# RFID_Arduino_REV04.net
KiCad netlist of a schematic drawn in EasyEDA Pro
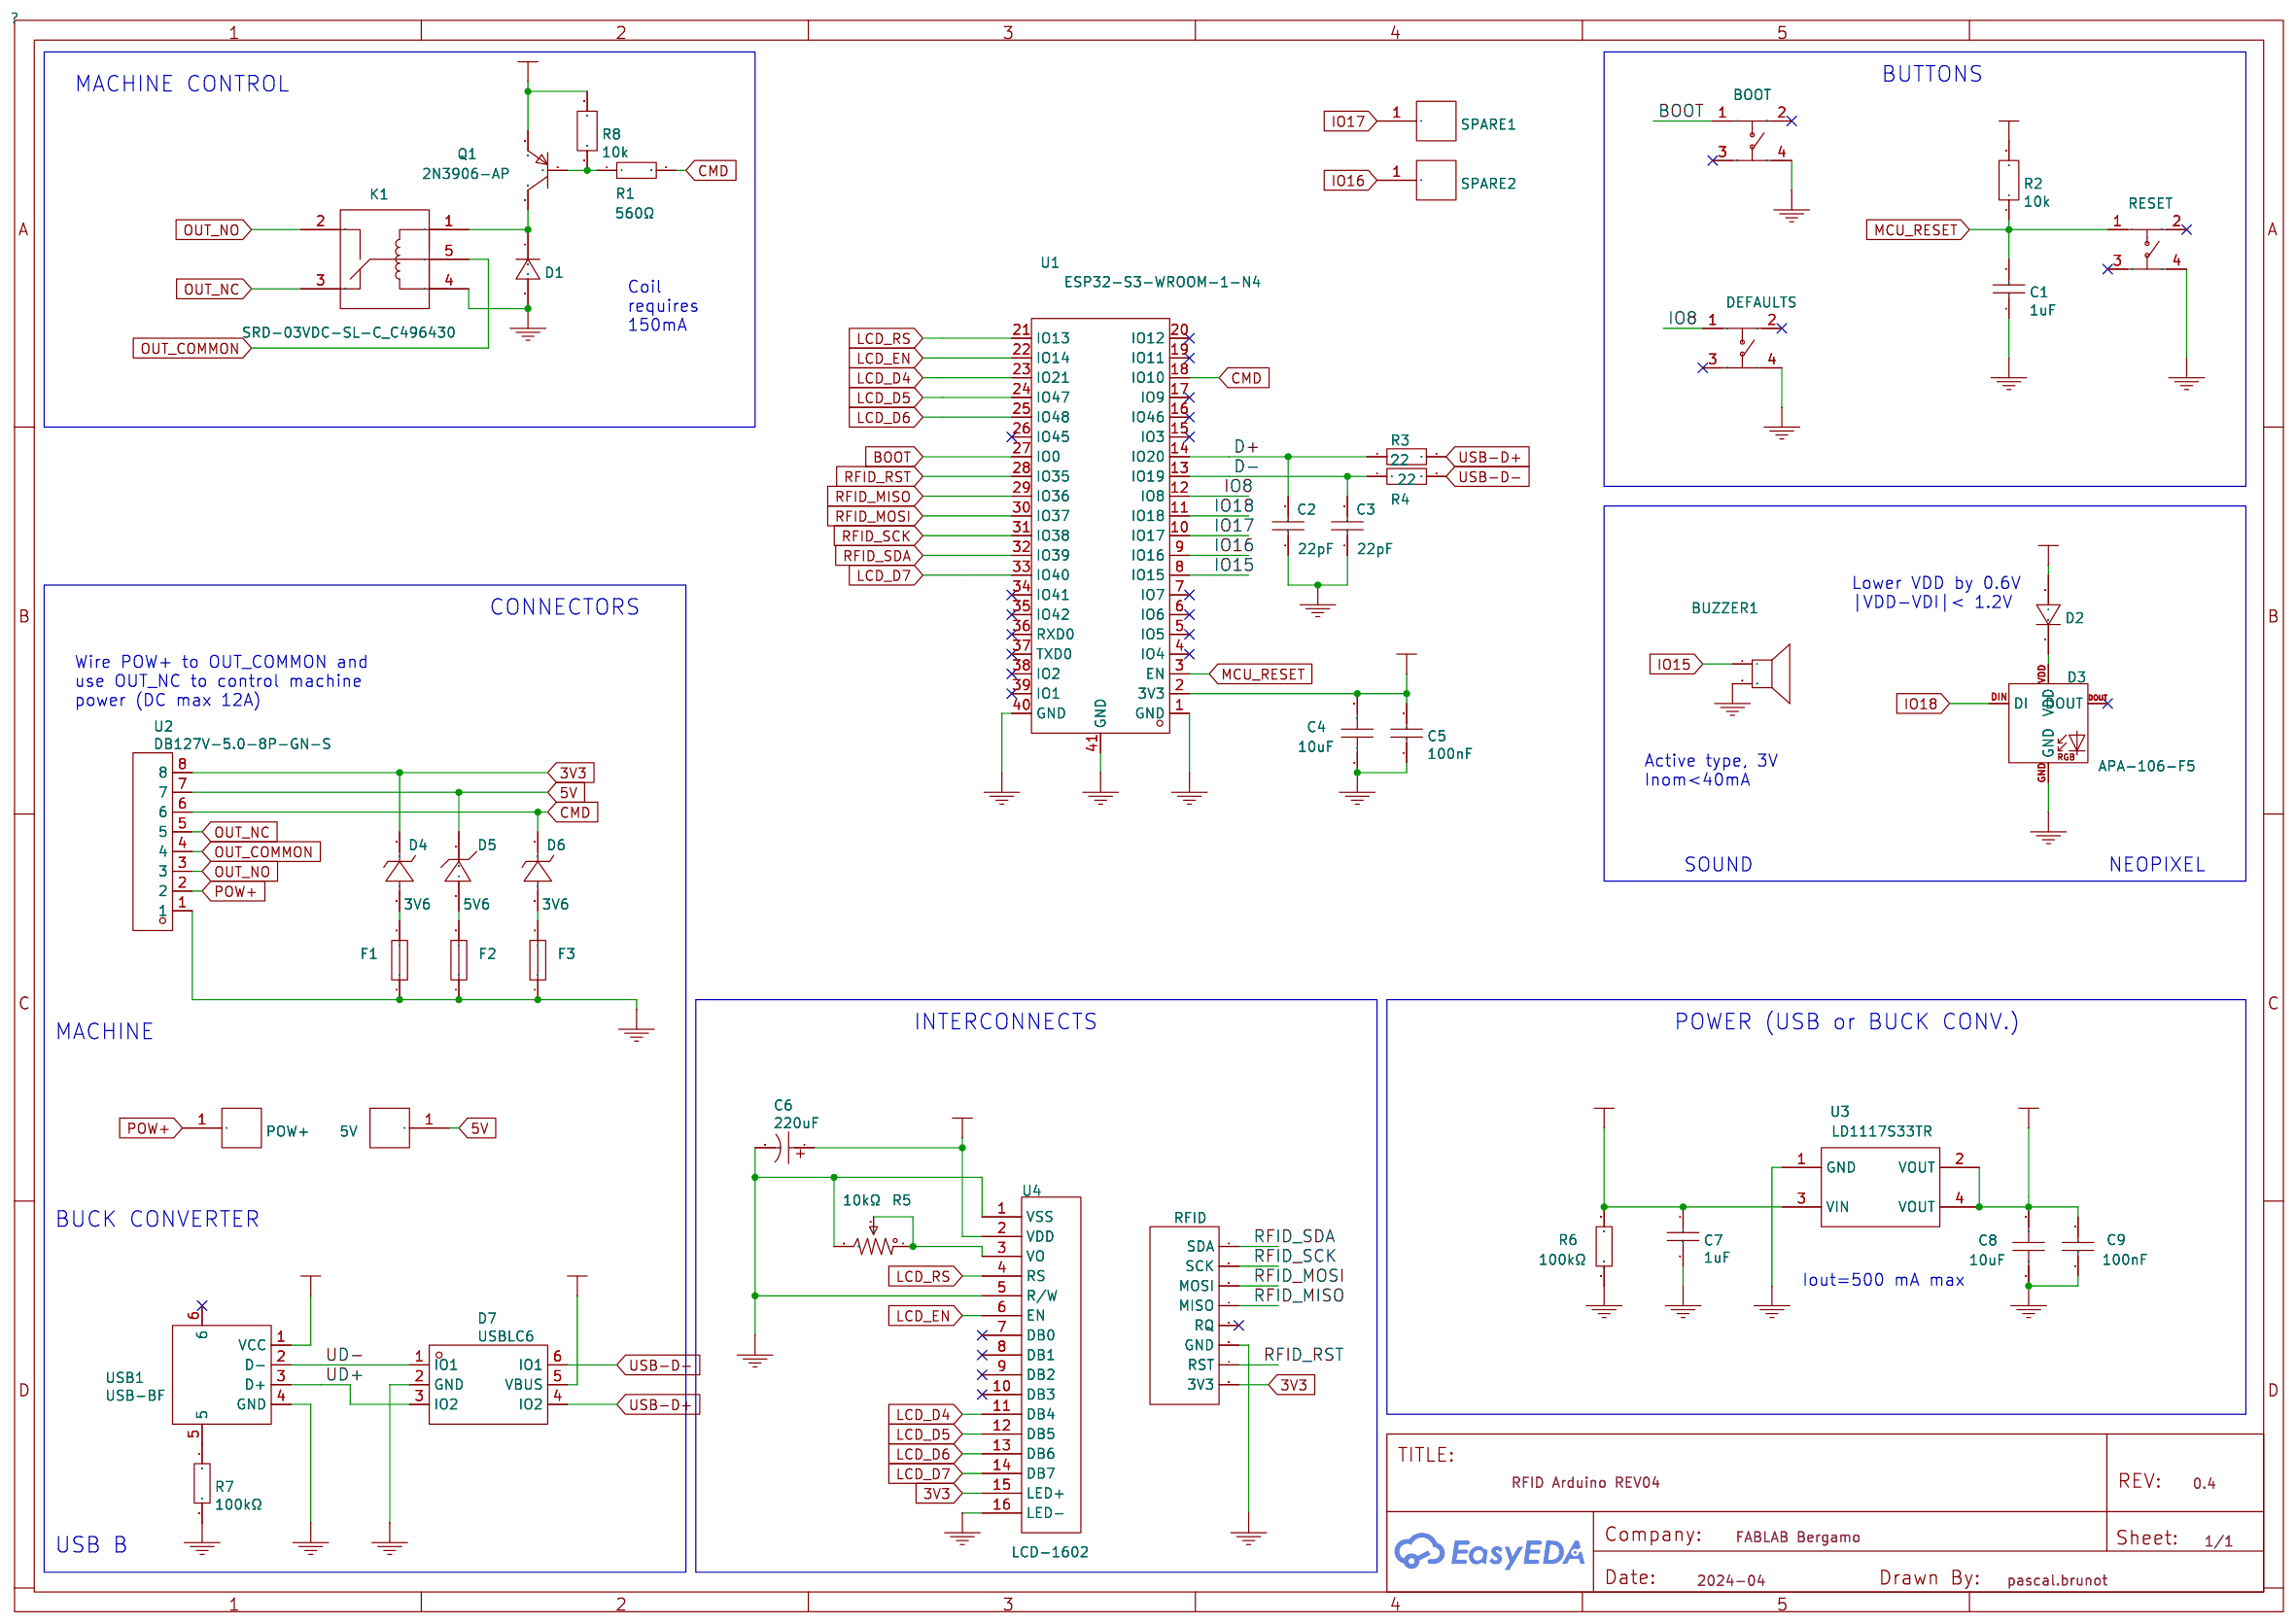
[diagram p0: schematic sheet]

(export (version "E")
  (design (tool "Eeschema 10.0.6"))
  (components
    (comp (ref "5V")
      (value "0577-0-43-80-21-27-10-0")
      (footprint "easyedapro:footprint_186c")
      (libsource (lib "easyedapro") (part "0577-0-43-80-21-27-10-0"))
    )
    (comp (ref "BOOT")
      (value "TS02-66-160-BK-260-LCR-D")
      (footprint "easyedapro:footprint_d5ca")
      (fields (field (name "Manufacturer") "CUI"))
      (libsource (lib "easyedapro") (part "TS02-66-160-BK-260-LCR-D"))
    )
    (comp (ref "BUZZER1")
      (value "4000Hz")
      (footprint "easyedapro:footprint_4700")
      (fields (field (name "Manufacturer Part") "SFN-12055PA6.5") (field (name "Manufacturer") "S&amp;S(海旭)"))
      (libsource (lib "easyedapro") (part "4000Hz"))
    )
    (comp (ref "C1")
      (value "1uF")
      (footprint "easyedapro:footprint_c612")
      (fields
        (field (name "Manufacturer Part") "CL21B105KBFNNNE")
        (field (name "Manufacturer") "SAMSUNG(三星)")
      )
      (libsource (lib "easyedapro") (part "1uF"))
    )
    (comp (ref "C2")
      (value "22pF")
      (footprint "easyedapro:footprint_7342")
      (fields (field (name "Manufacturer Part") "0402CG220J500NT") (field (name "Manufacturer") "FH(风华)"))
      (libsource (lib "easyedapro") (part "22pF"))
    )
    (comp (ref "C3")
      (value "22pF")
      (footprint "easyedapro:footprint_7342")
      (fields (field (name "Manufacturer Part") "0402CG220J500NT") (field (name "Manufacturer") "FH(风华)"))
      (libsource (lib "easyedapro") (part "22pF"))
    )
    (comp (ref "C4")
      (value "10uF")
      (footprint "easyedapro:footprint_c612")
      (fields
        (field (name "Manufacturer Part") "GRM21BR61H106KE43L")
        (field (name "Manufacturer") "muRata(村田)")
      )
      (libsource (lib "easyedapro") (part "10uF"))
    )
    (comp (ref "C5")
      (value "100nF")
      (footprint "easyedapro:footprint_c612")
      (fields
        (field (name "Manufacturer Part") "CL21B104KCFNNNE")
        (field (name "Manufacturer") "SAMSUNG(三星)")
      )
      (libsource (lib "easyedapro") (part "100nF"))
    )
    (comp (ref "C6")
      (value "220uF")
      (footprint "easyedapro:footprint_9de2")
      (fields (field (name "Manufacturer Part") "220uF 10V 5*7"))
      (libsource (lib "easyedapro") (part "220uF"))
    )
    (comp (ref "C7")
      (value "1uF")
      (footprint "easyedapro:footprint_c612")
      (fields
        (field (name "Manufacturer Part") "CL21B105KBFNNNE")
        (field (name "Manufacturer") "SAMSUNG(三星)")
      )
      (libsource (lib "easyedapro") (part "1uF"))
    )
    (comp (ref "C8")
      (value "10uF")
      (footprint "easyedapro:footprint_c612")
      (fields
        (field (name "Manufacturer Part") "GRM21BR61H106KE43L")
        (field (name "Manufacturer") "muRata(村田)")
      )
      (libsource (lib "easyedapro") (part "10uF"))
    )
    (comp (ref "C9")
      (value "100nF")
      (footprint "easyedapro:footprint_c612")
      (fields
        (field (name "Manufacturer Part") "CL21B104KCFNNNE")
        (field (name "Manufacturer") "SAMSUNG(三星)")
      )
      (libsource (lib "easyedapro") (part "100nF"))
    )
    (comp (ref "D1")
      (value "SM4007PL")
      (footprint "easyedapro:footprint_98a7")
      (fields (field (name "Manufacturer") "MDD"))
      (libsource (lib "easyedapro") (part "SM4007PL"))
    )
    (comp (ref "D2")
      (value "SM4007PL")
      (footprint "easyedapro:footprint_98a7")
      (fields (field (name "Manufacturer") "MDD"))
      (libsource (lib "easyedapro") (part "SM4007PL"))
    )
    (comp (ref "D3")
      (value "APA-106-F5")
      (footprint "easyedapro:footprint_7df5")
      (libsource (lib "easyedapro") (part "APA-106-F5"))
    )
    (comp (ref "D4")
      (value "3V6")
      (footprint "easyedapro:footprint_9df2")
      (fields (field (name "Manufacturer Part") "1SMA5914A") (field (name "Manufacturer") "LGE(鲁光)"))
      (libsource (lib "easyedapro") (part "3V6"))
    )
    (comp (ref "D5")
      (value "5V6")
      (footprint "easyedapro:footprint_7d78")
      (fields (field (name "Manufacturer Part") "ZMM5V6-M") (field (name "Manufacturer") "ST(先科)"))
      (libsource (lib "easyedapro") (part "5V6"))
    )
    (comp (ref "D6")
      (value "3V6")
      (footprint "easyedapro:footprint_9df2")
      (fields (field (name "Manufacturer Part") "1SMA5914A") (field (name "Manufacturer") "LGE(鲁光)"))
      (libsource (lib "easyedapro") (part "3V6"))
    )
    (comp (ref "D7")
      (value "USBLC6")
      (footprint "easyedapro:footprint_c63f")
      (fields
        (field (name "Manufacturer Part") "USBLC6-2SC6")
        (field (name "Manufacturer") "TECH PUBLIC(台舟)")
      )
      (libsource (lib "easyedapro") (part "USBLC6"))
    )
    (comp (ref "DEFAULTS")
      (value "TS02-66-160-BK-260-LCR-D")
      (footprint "easyedapro:footprint_d5ca")
      (fields (field (name "Manufacturer") "CUI"))
      (libsource (lib "easyedapro") (part "TS02-66-160-BK-260-LCR-D"))
    )
    (comp (ref "F1")
      (value "1206L016WR")
      (footprint "easyedapro:footprint_80a4")
      (fields (field (name "Manufacturer") "Littelfuse(美国力特)"))
      (libsource (lib "easyedapro") (part "1206L016WR"))
    )
    (comp (ref "F2")
      (value "1206L016WR")
      (footprint "easyedapro:footprint_80a4")
      (fields (field (name "Manufacturer") "Littelfuse(美国力特)"))
      (libsource (lib "easyedapro") (part "1206L016WR"))
    )
    (comp (ref "F3")
      (value "1206L016WR")
      (footprint "easyedapro:footprint_80a4")
      (fields (field (name "Manufacturer") "Littelfuse(美国力特)"))
      (libsource (lib "easyedapro") (part "1206L016WR"))
    )
    (comp (ref "K1")
      (value "SRD-03VDC-SL-C_C496430")
      (footprint "easyedapro:footprint_073f")
      (fields (field (name "Manufacturer Part") "SRD-03VDC-SL-C") (field (name "Manufacturer") "松乐"))
      (libsource (lib "easyedapro") (part "SRD-03VDC-SL-C_C496430"))
    )
    (comp (ref "P1")
      (value "RFID")
      (footprint "easyedapro:footprint_407f")
      (fields
        (field (name "Manufacturer Part") "Female headerHDR1X8-2.54")
        (field (name "Manufacturer") "BOOMELE")
      )
      (libsource (lib "easyedapro") (part "RFID"))
    )
    (comp (ref "POW+")
      (value "0577-0-43-80-21-27-10-0")
      (footprint "easyedapro:footprint_186c")
      (libsource (lib "easyedapro") (part "0577-0-43-80-21-27-10-0"))
    )
    (comp (ref "Q1")
      (value "2N3906-AP")
      (footprint "easyedapro:footprint_6217")
      (fields (field (name "Manufacturer") "MCC(美微科)"))
      (libsource (lib "easyedapro") (part "2N3906-AP"))
    )
    (comp (ref "R1")
      (value "560Ω")
      (footprint "easyedapro:footprint_ec5b")
      (fields
        (field (name "Manufacturer Part") "0805W8F5600T5E")
        (field (name "Manufacturer") "UNI-ROYAL(厚声)")
      )
      (libsource (lib "easyedapro") (part "560Ω"))
    )
    (comp (ref "R2")
      (value "10k")
      (footprint "easyedapro:footprint_7623")
      (fields
        (field (name "Manufacturer Part") "0805W8F1002T5E")
        (field (name "Manufacturer") "UNI-ROYAL(厚声)")
      )
      (libsource (lib "easyedapro") (part "10k"))
    )
    (comp (ref "R3")
      (value "22")
      (footprint "easyedapro:footprint_7623")
      (fields
        (field (name "Manufacturer Part") "0603WAF220JT5E")
        (field (name "Manufacturer") "UNI-ROYAL(厚声)")
      )
      (libsource (lib "easyedapro") (part "22"))
    )
    (comp (ref "R4")
      (value "22")
      (footprint "easyedapro:footprint_7623")
      (fields
        (field (name "Manufacturer Part") "0603WAF220JT5E")
        (field (name "Manufacturer") "UNI-ROYAL(厚声)")
      )
      (libsource (lib "easyedapro") (part "22"))
    )
    (comp (ref "R5")
      (value "10kΩ")
      (footprint "easyedapro:footprint_ac57")
      (fields (field (name "Manufacturer Part") "3296W-1-103") (field (name "Manufacturer") "BOCHEN(博晨)"))
      (libsource (lib "easyedapro") (part "10kΩ"))
    )
    (comp (ref "R6")
      (value "100kΩ")
      (footprint "easyedapro:footprint_ec5b")
      (fields
        (field (name "Manufacturer Part") "0805W8F1003T5E")
        (field (name "Manufacturer") "UNI-ROYAL(厚声)")
      )
      (libsource (lib "easyedapro") (part "100kΩ"))
    )
    (comp (ref "R7")
      (value "100kΩ")
      (footprint "easyedapro:footprint_ec5b")
      (fields
        (field (name "Manufacturer Part") "0805W8F1003T5E")
        (field (name "Manufacturer") "UNI-ROYAL(厚声)")
      )
      (libsource (lib "easyedapro") (part "100kΩ"))
    )
    (comp (ref "R8")
      (value "10k")
      (footprint "easyedapro:footprint_7623")
      (fields
        (field (name "Manufacturer Part") "0805W8F1002T5E")
        (field (name "Manufacturer") "UNI-ROYAL(厚声)")
      )
      (libsource (lib "easyedapro") (part "10k"))
    )
    (comp (ref "RESET")
      (value "TS02-66-160-BK-260-LCR-D")
      (footprint "easyedapro:footprint_d5ca")
      (fields (field (name "Manufacturer") "CUI"))
      (libsource (lib "easyedapro") (part "TS02-66-160-BK-260-LCR-D"))
    )
    (comp (ref "SPARE1")
      (value "0577-0-43-80-21-27-10-0")
      (footprint "easyedapro:footprint_186c")
      (libsource (lib "easyedapro") (part "0577-0-43-80-21-27-10-0"))
    )
    (comp (ref "SPARE2")
      (value "0577-0-43-80-21-27-10-0")
      (footprint "easyedapro:footprint_186c")
      (libsource (lib "easyedapro") (part "0577-0-43-80-21-27-10-0"))
    )
    (comp (ref "U1")
      (value "ESP32-S3-WROOM-1-N4")
      (footprint "easyedapro:footprint_15fb")
      (fields (field (name "Manufacturer") "ESPRESSIF(乐鑫)"))
      (libsource (lib "easyedapro") (part "ESP32-S3-WROOM-1-N4"))
    )
    (comp (ref "U2")
      (value "DB127V-5.0-8P-GN-S")
      (footprint "easyedapro:footprint_3f91")
      (fields (field (name "Manufacturer") "DORABO(地博电气)"))
      (libsource (lib "easyedapro") (part "DB127V-5.0-8P-GN-S"))
    )
    (comp (ref "U3")
      (value "LD1117S33TR")
      (footprint "easyedapro:footprint_bf77")
      (fields (field (name "Manufacturer") "ST(意法半导体)"))
      (libsource (lib "easyedapro") (part "LD1117S33TR"))
    )
    (comp (ref "U4")
      (value "LCD-1602")
      (footprint "easyedapro:footprint_ddb7")
      (fields (field (name "Manufacturer Part") "?"))
      (libsource (lib "easyedapro") (part "LCD-1602"))
    )
    (comp (ref "USB1")
      (value "USB-BF")
      (footprint "easyedapro:footprint_8114")
      (fields (field (name "Manufacturer Part") "670688000") (field (name "Manufacturer") "MOLEX"))
      (libsource (lib "easyedapro") (part "USB-BF"))
    )
  )
  (nets
    (net (code "1") (name "/D+") (class "Default")
      (node (ref "C2") (pin "2") (pinfunction "2_2") (pintype "input"))
      (node (ref "R3") (pin "1") (pinfunction "1_1") (pintype "input"))
      (node (ref "U1") (pin "14") (pinfunction "IO20_14") (pintype "unspecified"))
    )
    (net (code "2") (name "/D-") (class "Default")
      (node (ref "C3") (pin "2") (pinfunction "2_2") (pintype "input"))
      (node (ref "R4") (pin "1") (pinfunction "1_1") (pintype "input"))
      (node (ref "U1") (pin "13") (pinfunction "IO19_13") (pintype "unspecified"))
    )
    (net (code "3") (name "/IO8") (class "Default")
      (node (ref "DEFAULTS") (pin "1") (pinfunction "1_1") (pintype "unspecified"))
      (node (ref "U1") (pin "12") (pinfunction "IO8_12") (pintype "unspecified"))
    )
    (net (code "4") (name "/UD+") (class "Default")
      (node (ref "D7") (pin "3") (pinfunction "IO2_3") (pintype "unspecified"))
      (node (ref "USB1") (pin "3") (pinfunction "D+_3") (pintype "unspecified"))
    )
    (net (code "5") (name "/UD-") (class "Default")
      (node (ref "D7") (pin "1") (pinfunction "IO1_1") (pintype "unspecified"))
      (node (ref "USB1") (pin "2") (pinfunction "D-_2") (pintype "unspecified"))
    )
    (net (code "6") (name "3V3") (class "Default")
      (node (ref "C4") (pin "2") (pinfunction "2_2") (pintype "unspecified"))
      (node (ref "C5") (pin "2") (pinfunction "2_2") (pintype "input"))
      (node (ref "C8") (pin "2") (pinfunction "2_2") (pintype "unspecified"))
      (node (ref "C9") (pin "2") (pinfunction "2_2") (pintype "input"))
      (node (ref "D4") (pin "1") (pinfunction "C_1") (pintype "unspecified"))
      (node (ref "P1") (pin "8") (pinfunction "3V3_8") (pintype "input"))
      (node (ref "Q1") (pin "1") (pinfunction "1_1") (pintype "input"))
      (node (ref "R2") (pin "2") (pinfunction "2_2") (pintype "unspecified"))
      (node (ref "R8") (pin "2") (pinfunction "2_2") (pintype "unspecified"))
      (node (ref "U1") (pin "2") (pinfunction "3V3_2") (pintype "unspecified"))
      (node (ref "U2") (pin "8") (pinfunction "8_8") (pintype "unspecified"))
      (node (ref "U3") (pin "2") (pinfunction "VOUT_2") (pintype "unspecified"))
      (node (ref "U3") (pin "4") (pinfunction "VOUT_4") (pintype "unspecified"))
      (node (ref "U4") (pin "15") (pinfunction "LED+_15") (pintype "unspecified"))
    )
    (net (code "7") (name "5V") (class "Default")
      (node (ref "5V") (pin "1") (pinfunction "1_1") (pintype "unspecified"))
      (node (ref "C6") (pin "1") (pinfunction "1_1") (pintype "input"))
      (node (ref "C7") (pin "1") (pinfunction "1_1") (pintype "input"))
      (node (ref "D2") (pin "2") (pinfunction "A_2") (pintype "unspecified"))
      (node (ref "D5") (pin "1") (pinfunction "C_1") (pintype "unspecified"))
      (node (ref "D7") (pin "5") (pinfunction "VBUS_5") (pintype "unspecified"))
      (node (ref "R6") (pin "2") (pinfunction "2_2") (pintype "unspecified"))
      (node (ref "U2") (pin "7") (pinfunction "7_7") (pintype "unspecified"))
      (node (ref "U3") (pin "3") (pinfunction "VIN_3") (pintype "unspecified"))
      (node (ref "U4") (pin "2") (pinfunction "VDD_2") (pintype "unspecified"))
      (node (ref "USB1") (pin "1") (pinfunction "VCC_1") (pintype "unspecified"))
    )
    (net (code "8") (name "BOOT") (class "Default")
      (node (ref "BOOT") (pin "1") (pinfunction "1_1") (pintype "unspecified"))
      (node (ref "U1") (pin "27") (pinfunction "IO0_27") (pintype "unspecified"))
    )
    (net (code "9") (name "CMD") (class "Default")
      (node (ref "D6") (pin "1") (pinfunction "C_1") (pintype "unspecified"))
      (node (ref "R1") (pin "2") (pinfunction "2_2") (pintype "input"))
      (node (ref "U1") (pin "18") (pinfunction "IO10_18") (pintype "unspecified"))
      (node (ref "U2") (pin "6") (pinfunction "6_6") (pintype "unspecified"))
    )
    (net (code "10") (name "GND") (class "Default")
      (node (ref "BOOT") (pin "4") (pinfunction "4_4") (pintype "unspecified"))
      (node (ref "BUZZER1") (pin "2") (pinfunction "2_2") (pintype "unspecified"))
      (node (ref "C1") (pin "1") (pinfunction "1_1") (pintype "input"))
      (node (ref "C2") (pin "1") (pinfunction "1_1") (pintype "input"))
      (node (ref "C3") (pin "1") (pinfunction "1_1") (pintype "input"))
      (node (ref "C4") (pin "1") (pinfunction "1_1") (pintype "unspecified"))
      (node (ref "C5") (pin "1") (pinfunction "1_1") (pintype "input"))
      (node (ref "C6") (pin "2") (pinfunction "2_2") (pintype "input"))
      (node (ref "C7") (pin "2") (pinfunction "2_2") (pintype "input"))
      (node (ref "C8") (pin "1") (pinfunction "1_1") (pintype "unspecified"))
      (node (ref "C9") (pin "1") (pinfunction "1_1") (pintype "input"))
      (node (ref "D1") (pin "2") (pinfunction "A_2") (pintype "unspecified"))
      (node (ref "D3") (pin "GND") (pinfunction "GND_GND") (pintype "bidirectional"))
      (node (ref "D7") (pin "2") (pinfunction "GND_2") (pintype "unspecified"))
      (node (ref "DEFAULTS") (pin "4") (pinfunction "4_4") (pintype "unspecified"))
      (node (ref "F1") (pin "1") (pinfunction "1_1") (pintype "unspecified"))
      (node (ref "F2") (pin "1") (pinfunction "1_1") (pintype "unspecified"))
      (node (ref "F3") (pin "1") (pinfunction "1_1") (pintype "unspecified"))
      (node (ref "K1") (pin "4") (pinfunction "4_4") (pintype "unspecified"))
      (node (ref "P1") (pin "6") (pinfunction "GND_6") (pintype "input"))
      (node (ref "R5") (pin "3") (pinfunction "3_3") (pintype "unspecified"))
      (node (ref "R6") (pin "1") (pinfunction "1_1") (pintype "unspecified"))
      (node (ref "R7") (pin "2") (pinfunction "2_2") (pintype "unspecified"))
      (node (ref "RESET") (pin "4") (pinfunction "4_4") (pintype "unspecified"))
      (node (ref "U1") (pin "1") (pinfunction "GND_1") (pintype "unspecified"))
      (node (ref "U1") (pin "40") (pinfunction "GND_40") (pintype "unspecified"))
      (node (ref "U1") (pin "41") (pinfunction "GND_41") (pintype "unspecified"))
      (node (ref "U2") (pin "1") (pinfunction "1_1") (pintype "unspecified"))
      (node (ref "U3") (pin "1") (pinfunction "GND_1") (pintype "unspecified"))
      (node (ref "U4") (pin "1") (pinfunction "VSS_1") (pintype "unspecified"))
      (node (ref "U4") (pin "16") (pinfunction "LED-_16") (pintype "unspecified"))
      (node (ref "U4") (pin "5") (pinfunction "R/W_5") (pintype "unspecified"))
      (node (ref "USB1") (pin "4") (pinfunction "GND_4") (pintype "unspecified"))
    )
    (net (code "11") (name "IO15") (class "Default")
      (node (ref "BUZZER1") (pin "1") (pinfunction "1_1") (pintype "unspecified"))
      (node (ref "U1") (pin "8") (pinfunction "IO15_8") (pintype "unspecified"))
    )
    (net (code "12") (name "IO16") (class "Default")
      (node (ref "SPARE2") (pin "1") (pinfunction "1_1") (pintype "unspecified"))
      (node (ref "U1") (pin "9") (pinfunction "IO16_9") (pintype "unspecified"))
    )
    (net (code "13") (name "IO17") (class "Default")
      (node (ref "SPARE1") (pin "1") (pinfunction "1_1") (pintype "unspecified"))
      (node (ref "U1") (pin "10") (pinfunction "IO17_10") (pintype "unspecified"))
    )
    (net (code "14") (name "IO18") (class "Default")
      (node (ref "D3") (pin "DIN") (pinfunction "DI_DIN") (pintype "input"))
      (node (ref "U1") (pin "11") (pinfunction "IO18_11") (pintype "unspecified"))
    )
    (net (code "15") (name "LCD_D4") (class "Default")
      (node (ref "U1") (pin "23") (pinfunction "IO21_23") (pintype "unspecified"))
      (node (ref "U4") (pin "11") (pinfunction "DB4_11") (pintype "unspecified"))
    )
    (net (code "16") (name "LCD_D5") (class "Default")
      (node (ref "U1") (pin "24") (pinfunction "IO47_24") (pintype "unspecified"))
      (node (ref "U4") (pin "12") (pinfunction "DB5_12") (pintype "unspecified"))
    )
    (net (code "17") (name "LCD_D6") (class "Default")
      (node (ref "U1") (pin "25") (pinfunction "IO48_25") (pintype "unspecified"))
      (node (ref "U4") (pin "13") (pinfunction "DB6_13") (pintype "unspecified"))
    )
    (net (code "18") (name "LCD_D7") (class "Default")
      (node (ref "U1") (pin "33") (pinfunction "IO40_33") (pintype "unspecified"))
      (node (ref "U4") (pin "14") (pinfunction "DB7_14") (pintype "unspecified"))
    )
    (net (code "19") (name "LCD_EN") (class "Default")
      (node (ref "U1") (pin "22") (pinfunction "IO14_22") (pintype "unspecified"))
      (node (ref "U4") (pin "6") (pinfunction "EN_6") (pintype "unspecified"))
    )
    (net (code "20") (name "LCD_RS") (class "Default")
      (node (ref "U1") (pin "21") (pinfunction "IO13_21") (pintype "unspecified"))
      (node (ref "U4") (pin "4") (pinfunction "RS_4") (pintype "unspecified"))
    )
    (net (code "21") (name "MCU_RESET") (class "Default")
      (node (ref "C1") (pin "2") (pinfunction "2_2") (pintype "input"))
      (node (ref "R2") (pin "1") (pinfunction "1_1") (pintype "unspecified"))
      (node (ref "RESET") (pin "1") (pinfunction "1_1") (pintype "unspecified"))
      (node (ref "U1") (pin "3") (pinfunction "EN_3") (pintype "unspecified"))
    )
    (net (code "22") (name "Net-(D1-C)") (class "Default")
      (node (ref "D1") (pin "1") (pinfunction "C_1") (pintype "unspecified"))
      (node (ref "K1") (pin "1") (pinfunction "1_1") (pintype "unspecified"))
      (node (ref "Q1") (pin "3") (pinfunction "3_3") (pintype "input"))
    )
    (net (code "23") (name "Net-(D2-C)") (class "Default")
      (node (ref "D2") (pin "1") (pinfunction "C_1") (pintype "unspecified"))
      (node (ref "D3") (pin "VDD") (pinfunction "VDD_VDD") (pintype "bidirectional"))
    )
    (net (code "24") (name "Net-(D4-A)") (class "Default")
      (node (ref "D4") (pin "2") (pinfunction "A_2") (pintype "unspecified"))
      (node (ref "F1") (pin "2") (pinfunction "2_2") (pintype "unspecified"))
    )
    (net (code "25") (name "Net-(D5-A)") (class "Default")
      (node (ref "D5") (pin "2") (pinfunction "A_2") (pintype "unspecified"))
      (node (ref "F2") (pin "2") (pinfunction "2_2") (pintype "unspecified"))
    )
    (net (code "26") (name "Net-(D6-A)") (class "Default")
      (node (ref "D6") (pin "2") (pinfunction "A_2") (pintype "unspecified"))
      (node (ref "F3") (pin "2") (pinfunction "2_2") (pintype "unspecified"))
    )
    (net (code "27") (name "Net-(Q1-Pad2)") (class "Default")
      (node (ref "Q1") (pin "2") (pinfunction "2_2") (pintype "input"))
      (node (ref "R1") (pin "1") (pinfunction "1_1") (pintype "input"))
      (node (ref "R8") (pin "1") (pinfunction "1_1") (pintype "unspecified"))
    )
    (net (code "28") (name "Net-(R7-Pad1)") (class "Default")
      (node (ref "R7") (pin "1") (pinfunction "1_1") (pintype "unspecified"))
      (node (ref "USB1") (pin "5") (pinfunction "5_5") (pintype "unspecified"))
    )
    (net (code "29") (name "Net-(U4-VO)") (class "Default")
      (node (ref "R5") (pin "1") (pinfunction "1_1") (pintype "unspecified"))
      (node (ref "R5") (pin "2") (pinfunction "2_2") (pintype "unspecified"))
      (node (ref "U4") (pin "3") (pinfunction "VO_3") (pintype "unspecified"))
    )
    (net (code "30") (name "OUT_COMMON") (class "Default")
      (node (ref "K1") (pin "5") (pinfunction "5_5") (pintype "unspecified"))
      (node (ref "U2") (pin "4") (pinfunction "4_4") (pintype "unspecified"))
    )
    (net (code "31") (name "OUT_NC") (class "Default")
      (node (ref "K1") (pin "3") (pinfunction "3_3") (pintype "unspecified"))
      (node (ref "U2") (pin "5") (pinfunction "5_5") (pintype "unspecified"))
    )
    (net (code "32") (name "OUT_NO") (class "Default")
      (node (ref "K1") (pin "2") (pinfunction "2_2") (pintype "unspecified"))
      (node (ref "U2") (pin "3") (pinfunction "3_3") (pintype "unspecified"))
    )
    (net (code "33") (name "POW+") (class "Default")
      (node (ref "POW+") (pin "1") (pinfunction "1_1") (pintype "unspecified"))
      (node (ref "U2") (pin "2") (pinfunction "2_2") (pintype "unspecified"))
    )
    (net (code "34") (name "RFID_MISO") (class "Default")
      (node (ref "P1") (pin "4") (pinfunction "MISO_4") (pintype "input"))
      (node (ref "U1") (pin "29") (pinfunction "IO36_29") (pintype "unspecified"))
    )
    (net (code "35") (name "RFID_MOSI") (class "Default")
      (node (ref "P1") (pin "3") (pinfunction "MOSI_3") (pintype "input"))
      (node (ref "U1") (pin "30") (pinfunction "IO37_30") (pintype "unspecified"))
    )
    (net (code "36") (name "RFID_RST") (class "Default")
      (node (ref "P1") (pin "7") (pinfunction "RST_7") (pintype "input"))
      (node (ref "U1") (pin "28") (pinfunction "IO35_28") (pintype "unspecified"))
    )
    (net (code "37") (name "RFID_SCK") (class "Default")
      (node (ref "P1") (pin "2") (pinfunction "SCK_2") (pintype "input"))
      (node (ref "U1") (pin "31") (pinfunction "IO38_31") (pintype "unspecified"))
    )
    (net (code "38") (name "RFID_SDA") (class "Default")
      (node (ref "P1") (pin "1") (pinfunction "SDA_1") (pintype "input"))
      (node (ref "U1") (pin "32") (pinfunction "IO39_32") (pintype "unspecified"))
    )
    (net (code "39") (name "USB-D+") (class "Default")
      (node (ref "D7") (pin "4") (pinfunction "IO2_4") (pintype "unspecified"))
      (node (ref "R3") (pin "2") (pinfunction "2_2") (pintype "input"))
    )
    (net (code "40") (name "USB-D-") (class "Default")
      (node (ref "D7") (pin "6") (pinfunction "IO1_6") (pintype "unspecified"))
      (node (ref "R4") (pin "2") (pinfunction "2_2") (pintype "input"))
    )
    (net (code "41") (name "unconnected-(BOOT-Pad2)") (class "Default")
      (node (ref "BOOT") (pin "2") (pinfunction "2_2") (pintype "unspecified+no_connect"))
    )
    (net (code "42") (name "unconnected-(BOOT-Pad3)") (class "Default")
      (node (ref "BOOT") (pin "3") (pinfunction "3_3") (pintype "unspecified+no_connect"))
    )
    (net (code "43") (name "unconnected-(D3-PadDOUT)") (class "Default")
      (node (ref "D3") (pin "DOUT") (pinfunction "DOUT_DOUT") (pintype "output+no_connect"))
    )
    (net (code "44") (name "unconnected-(DEFAULTS-Pad2)") (class "Default")
      (node (ref "DEFAULTS") (pin "2") (pinfunction "2_2") (pintype "unspecified+no_connect"))
    )
    (net (code "45") (name "unconnected-(DEFAULTS-Pad3)") (class "Default")
      (node (ref "DEFAULTS") (pin "3") (pinfunction "3_3") (pintype "unspecified+no_connect"))
    )
    (net (code "46") (name "unconnected-(P1-RQ-Pad5)") (class "Default")
      (node (ref "P1") (pin "5") (pinfunction "RQ_5") (pintype "input+no_connect"))
    )
    (net (code "47") (name "unconnected-(RESET-Pad2)") (class "Default")
      (node (ref "RESET") (pin "2") (pinfunction "2_2") (pintype "unspecified+no_connect"))
    )
    (net (code "48") (name "unconnected-(RESET-Pad3)") (class "Default")
      (node (ref "RESET") (pin "3") (pinfunction "3_3") (pintype "unspecified+no_connect"))
    )
    (net (code "49") (name "unconnected-(U1-IO1-Pad39)") (class "Default")
      (node (ref "U1") (pin "39") (pinfunction "IO1_39") (pintype "unspecified+no_connect"))
    )
    (net (code "50") (name "unconnected-(U1-IO2-Pad38)") (class "Default")
      (node (ref "U1") (pin "38") (pinfunction "IO2_38") (pintype "unspecified+no_connect"))
    )
    (net (code "51") (name "unconnected-(U1-IO3-Pad15)") (class "Default")
      (node (ref "U1") (pin "15") (pinfunction "IO3_15") (pintype "unspecified+no_connect"))
    )
    (net (code "52") (name "unconnected-(U1-IO4-Pad4)") (class "Default")
      (node (ref "U1") (pin "4") (pinfunction "IO4_4") (pintype "unspecified+no_connect"))
    )
    (net (code "53") (name "unconnected-(U1-IO5-Pad5)") (class "Default")
      (node (ref "U1") (pin "5") (pinfunction "IO5_5") (pintype "unspecified+no_connect"))
    )
    (net (code "54") (name "unconnected-(U1-IO6-Pad6)") (class "Default")
      (node (ref "U1") (pin "6") (pinfunction "IO6_6") (pintype "unspecified+no_connect"))
    )
    (net (code "55") (name "unconnected-(U1-IO7-Pad7)") (class "Default")
      (node (ref "U1") (pin "7") (pinfunction "IO7_7") (pintype "unspecified+no_connect"))
    )
    (net (code "56") (name "unconnected-(U1-IO9-Pad17)") (class "Default")
      (node (ref "U1") (pin "17") (pinfunction "IO9_17") (pintype "unspecified+no_connect"))
    )
    (net (code "57") (name "unconnected-(U1-IO11-Pad19)") (class "Default")
      (node (ref "U1") (pin "19") (pinfunction "IO11_19") (pintype "unspecified+no_connect"))
    )
    (net (code "58") (name "unconnected-(U1-IO12-Pad20)") (class "Default")
      (node (ref "U1") (pin "20") (pinfunction "IO12_20") (pintype "unspecified+no_connect"))
    )
    (net (code "59") (name "unconnected-(U1-IO41-Pad34)") (class "Default")
      (node (ref "U1") (pin "34") (pinfunction "IO41_34") (pintype "unspecified+no_connect"))
    )
    (net (code "60") (name "unconnected-(U1-IO42-Pad35)") (class "Default")
      (node (ref "U1") (pin "35") (pinfunction "IO42_35") (pintype "unspecified+no_connect"))
    )
    (net (code "61") (name "unconnected-(U1-IO45-Pad26)") (class "Default")
      (node (ref "U1") (pin "26") (pinfunction "IO45_26") (pintype "unspecified+no_connect"))
    )
    (net (code "62") (name "unconnected-(U1-IO46-Pad16)") (class "Default")
      (node (ref "U1") (pin "16") (pinfunction "IO46_16") (pintype "unspecified+no_connect"))
    )
    (net (code "63") (name "unconnected-(U1-RXD0-Pad36)") (class "Default")
      (node (ref "U1") (pin "36") (pinfunction "RXD0_36") (pintype "unspecified+no_connect"))
    )
    (net (code "64") (name "unconnected-(U1-TXD0-Pad37)") (class "Default")
      (node (ref "U1") (pin "37") (pinfunction "TXD0_37") (pintype "unspecified+no_connect"))
    )
    (net (code "65") (name "unconnected-(U4-DB0-Pad7)") (class "Default")
      (node (ref "U4") (pin "7") (pinfunction "DB0_7") (pintype "unspecified+no_connect"))
    )
    (net (code "66") (name "unconnected-(U4-DB1-Pad8)") (class "Default")
      (node (ref "U4") (pin "8") (pinfunction "DB1_8") (pintype "unspecified+no_connect"))
    )
    (net (code "67") (name "unconnected-(U4-DB2-Pad9)") (class "Default")
      (node (ref "U4") (pin "9") (pinfunction "DB2_9") (pintype "unspecified+no_connect"))
    )
    (net (code "68") (name "unconnected-(U4-DB3-Pad10)") (class "Default")
      (node (ref "U4") (pin "10") (pinfunction "DB3_10") (pintype "unspecified+no_connect"))
    )
    (net (code "69") (name "unconnected-(USB1-Pad6)") (class "Default")
      (node (ref "USB1") (pin "6") (pinfunction "6_6") (pintype "unspecified+no_connect"))
    )
  )
)
